# control_pipe_v2.net
KiCad netlist of a schematic drawn in EAGLE
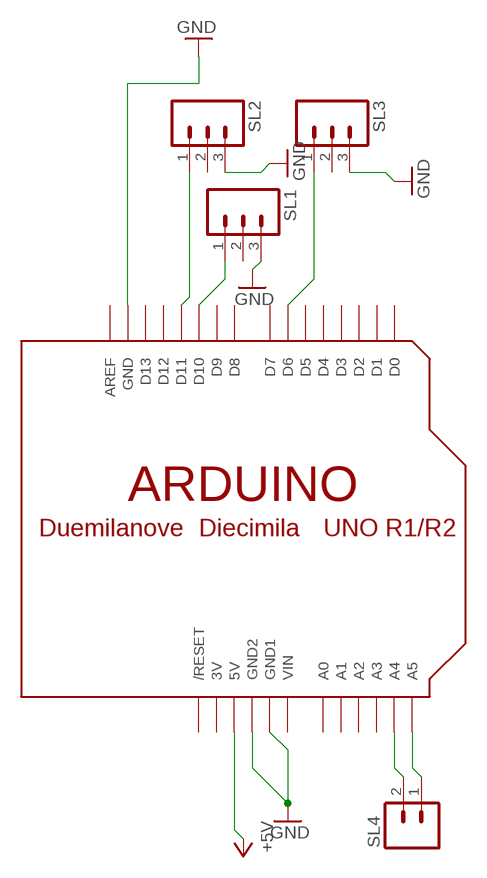
[diagram p0: schematic, sheet 1]

(export (version "E")
  (design (tool "Eeschema 10.0.6"))
  (components
    (comp (ref "SL1")
      (value "M03")
      (footprint "eagle-import:03P")
      (libsource (lib "eagle-import") (part "M03"))
    )
    (comp (ref "SL2")
      (value "M03")
      (footprint "eagle-import:03P")
      (libsource (lib "eagle-import") (part "M03"))
    )
    (comp (ref "SL3")
      (value "M03")
      (footprint "eagle-import:03P")
      (libsource (lib "eagle-import") (part "M03"))
    )
    (comp (ref "SL4")
      (value "M02")
      (footprint "eagle-import:02P")
      (libsource (lib "eagle-import") (part "M02"))
    )
    (comp (ref "U$1")
      (value "ARDUINO-NODIM")
      (footprint "eagle-import:ARDUINO-NODIM")
      (libsource (lib "eagle-import") (part "ARDUINO-NODIM"))
    )
  )
  (nets
    (net (code "1") (name "+5V") (class "Default")
      (node (ref "U$1") (pin "5V") (pinfunction "5V_5V") (pintype "power_in"))
    )
    (net (code "2") (name "/3V") (class "Default")
      (node (ref "U$1") (pin "3V") (pinfunction "3V_3V") (pintype "power_in"))
    )
    (net (code "3") (name "/VIN") (class "Default")
      (node (ref "U$1") (pin "VIN") (pinfunction "VIN_VIN") (pintype "power_in"))
    )
    (net (code "4") (name "GND") (class "Default")
      (node (ref "SL1") (pin "3") (pinfunction "3_3") (pintype "passive"))
      (node (ref "SL2") (pin "3") (pinfunction "3_3") (pintype "passive"))
      (node (ref "SL3") (pin "3") (pinfunction "3_3") (pintype "passive"))
      (node (ref "U$1") (pin "GND") (pinfunction "GND_GND") (pintype "power_in"))
      (node (ref "U$1") (pin "GND1") (pinfunction "GND1_GND1") (pintype "power_in"))
      (node (ref "U$1") (pin "GND2") (pinfunction "GND2_GND2") (pintype "power_in"))
    )
    (net (code "5") (name "Net-(SL1-Pad1)") (class "Default")
      (node (ref "SL1") (pin "1") (pinfunction "1_1") (pintype "passive"))
      (node (ref "U$1") (pin "D10") (pinfunction "D10_D10") (pintype "bidirectional"))
    )
    (net (code "6") (name "Net-(SL2-Pad1)") (class "Default")
      (node (ref "SL2") (pin "1") (pinfunction "1_1") (pintype "passive"))
      (node (ref "U$1") (pin "D11") (pinfunction "D11_D11") (pintype "bidirectional"))
    )
    (net (code "7") (name "Net-(SL3-Pad1)") (class "Default")
      (node (ref "SL3") (pin "1") (pinfunction "1_1") (pintype "passive"))
      (node (ref "U$1") (pin "D6") (pinfunction "D6_D6") (pintype "bidirectional"))
    )
    (net (code "8") (name "Net-(SL4-Pad1)") (class "Default")
      (node (ref "SL4") (pin "1") (pinfunction "1_1") (pintype "passive"))
      (node (ref "U$1") (pin "A5") (pinfunction "A5_A5") (pintype "bidirectional"))
    )
    (net (code "9") (name "Net-(SL4-Pad2)") (class "Default")
      (node (ref "SL4") (pin "2") (pinfunction "2_2") (pintype "passive"))
      (node (ref "U$1") (pin "A4") (pinfunction "A4_A4") (pintype "bidirectional"))
    )
    (net (code "10") (name "unconnected-(SL1-Pad2)") (class "Default")
      (node (ref "SL1") (pin "2") (pinfunction "2_2") (pintype "passive"))
    )
    (net (code "11") (name "unconnected-(SL2-Pad2)") (class "Default")
      (node (ref "SL2") (pin "2") (pinfunction "2_2") (pintype "passive"))
    )
    (net (code "12") (name "unconnected-(SL3-Pad2)") (class "Default")
      (node (ref "SL3") (pin "2") (pinfunction "2_2") (pintype "passive"))
    )
    (net (code "13") (name "unconnected-(U$1-PadA0)") (class "Default")
      (node (ref "U$1") (pin "A0") (pinfunction "A0_A0") (pintype "bidirectional"))
    )
    (net (code "14") (name "unconnected-(U$1-PadA1)") (class "Default")
      (node (ref "U$1") (pin "A1") (pinfunction "A1_A1") (pintype "bidirectional"))
    )
    (net (code "15") (name "unconnected-(U$1-PadA2)") (class "Default")
      (node (ref "U$1") (pin "A2") (pinfunction "A2_A2") (pintype "bidirectional"))
    )
    (net (code "16") (name "unconnected-(U$1-PadA3)") (class "Default")
      (node (ref "U$1") (pin "A3") (pinfunction "A3_A3") (pintype "bidirectional"))
    )
    (net (code "17") (name "unconnected-(U$1-PadAREF)") (class "Default")
      (node (ref "U$1") (pin "AREF") (pinfunction "AREF_AREF") (pintype "bidirectional"))
    )
    (net (code "18") (name "unconnected-(U$1-PadD0)") (class "Default")
      (node (ref "U$1") (pin "D0") (pinfunction "D0_D0") (pintype "bidirectional"))
    )
    (net (code "19") (name "unconnected-(U$1-PadD1)") (class "Default")
      (node (ref "U$1") (pin "D1") (pinfunction "D1_D1") (pintype "bidirectional"))
    )
    (net (code "20") (name "unconnected-(U$1-PadD2)") (class "Default")
      (node (ref "U$1") (pin "D2") (pinfunction "D2_D2") (pintype "bidirectional"))
    )
    (net (code "21") (name "unconnected-(U$1-PadD3)") (class "Default")
      (node (ref "U$1") (pin "D3") (pinfunction "D3_D3") (pintype "bidirectional"))
    )
    (net (code "22") (name "unconnected-(U$1-PadD4)") (class "Default")
      (node (ref "U$1") (pin "D4") (pinfunction "D4_D4") (pintype "bidirectional"))
    )
    (net (code "23") (name "unconnected-(U$1-PadD5)") (class "Default")
      (node (ref "U$1") (pin "D5") (pinfunction "D5_D5") (pintype "bidirectional"))
    )
    (net (code "24") (name "unconnected-(U$1-PadD7)") (class "Default")
      (node (ref "U$1") (pin "D7") (pinfunction "D7_D7") (pintype "bidirectional"))
    )
    (net (code "25") (name "unconnected-(U$1-PadD8)") (class "Default")
      (node (ref "U$1") (pin "D8") (pinfunction "D8_D8") (pintype "bidirectional"))
    )
    (net (code "26") (name "unconnected-(U$1-PadD9)") (class "Default")
      (node (ref "U$1") (pin "D9") (pinfunction "D9_D9") (pintype "bidirectional"))
    )
    (net (code "27") (name "unconnected-(U$1-PadD12)") (class "Default")
      (node (ref "U$1") (pin "D12") (pinfunction "D12_D12") (pintype "bidirectional"))
    )
    (net (code "28") (name "unconnected-(U$1-PadD13)") (class "Default")
      (node (ref "U$1") (pin "D13") (pinfunction "D13_D13") (pintype "bidirectional"))
    )
    (net (code "29") (name "unconnected-(U$1-{slash}RESET-PadRESET)") (class "Default")
      (node (ref "U$1") (pin "RESET") (pinfunction "/RESET_RESET") (pintype "bidirectional"))
    )
  )
)
